# IAS_v006.net
KiCad netlist of a schematic drawn in EAGLE
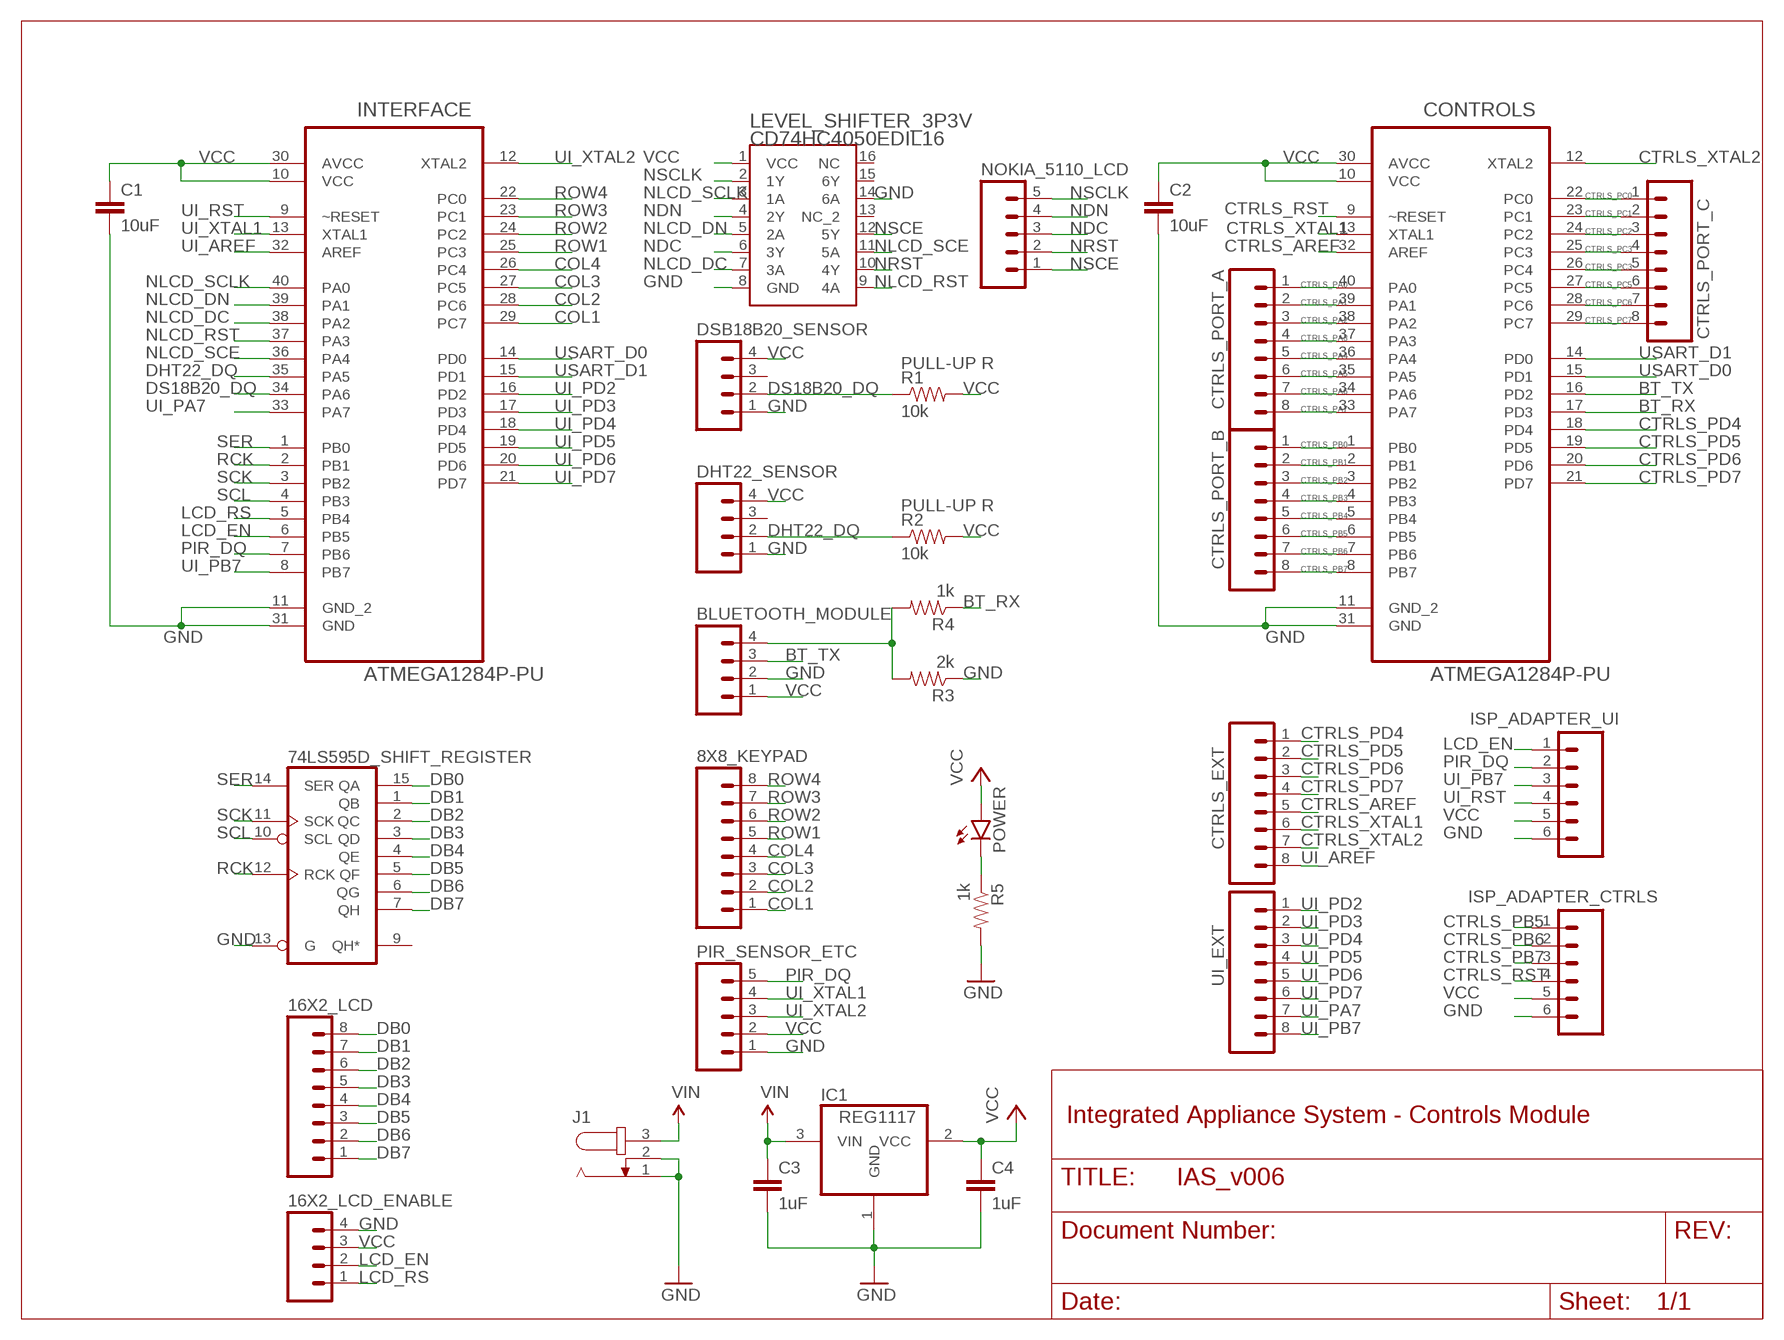
[diagram p0: schematic, sheet 1]

(export (version "E")
  (design (tool "Eeschema 10.0.6"))
  (components
    (comp (ref "8X8_KEYPAD")
      (value "M08")
      (footprint "eagle-import:1X08_ROUND")
      (libsource (lib "eagle-import") (part "M08"))
    )
    (comp (ref "16X2_LCD")
      (value "M08")
      (footprint "eagle-import:1X08_ROUND")
      (libsource (lib "eagle-import") (part "M08"))
    )
    (comp (ref "16X2_LCD_ENABLE")
      (value "M04NO_SILK_ALL_ROUND")
      (footprint "eagle-import:1X04_NO_SILK_ALL_ROUND")
      (libsource (lib "eagle-import") (part "M04NO_SILK_ALL_ROUND"))
    )
    (comp (ref "74LS595D_SHIFT_REGISTER")
      (value "74LS595N")
      (footprint "eagle-import:DIL16")
      (fields (field (name "MPN") "SN74LS595D"))
      (libsource (lib "eagle-import") (part "74595NLS"))
    )
    (comp (ref "BLUETOOTH_MODULE")
      (value "M04NO_SILK_ALL_ROUND")
      (footprint "eagle-import:1X04_NO_SILK_ALL_ROUND")
      (libsource (lib "eagle-import") (part "M04NO_SILK_ALL_ROUND"))
    )
    (comp (ref "C1")
      (value "10uF")
      (footprint "eagle-import:1206")
      (libsource (lib "eagle-import") (part "CAP1206"))
    )
    (comp (ref "C2")
      (value "10uF")
      (footprint "eagle-import:1206")
      (libsource (lib "eagle-import") (part "CAP1206"))
    )
    (comp (ref "C3")
      (value "1uF")
      (footprint "eagle-import:1206")
      (libsource (lib "eagle-import") (part "CAP1206"))
    )
    (comp (ref "C4")
      (value "1uF")
      (footprint "eagle-import:1206")
      (libsource (lib "eagle-import") (part "CAP1206"))
    )
    (comp (ref "CONTROLS")
      (value "ATMEGA1284P-PU")
      (footprint "eagle-import:DIP254P1524X483-40")
      (libsource (lib "eagle-import") (part "ATMEGA1284P-PU"))
    )
    (comp (ref "CTRLS_EXT")
      (value "M08")
      (footprint "eagle-import:1X08_ROUND")
      (libsource (lib "eagle-import") (part "M08"))
    )
    (comp (ref "CTRLS_PORT_A")
      (value "M08")
      (footprint "eagle-import:1X08_ROUND")
      (libsource (lib "eagle-import") (part "M08"))
    )
    (comp (ref "CTRLS_PORT_B")
      (value "M08")
      (footprint "eagle-import:1X08_ROUND")
      (libsource (lib "eagle-import") (part "M08"))
    )
    (comp (ref "CTRLS_PORT_C")
      (value "M08")
      (footprint "eagle-import:1X08_ROUND")
      (libsource (lib "eagle-import") (part "M08"))
    )
    (comp (ref "DHT22_SENSOR")
      (value "M04NO_SILK_ALL_ROUND")
      (footprint "eagle-import:1X04_NO_SILK_ALL_ROUND")
      (libsource (lib "eagle-import") (part "M04NO_SILK_ALL_ROUND"))
    )
    (comp (ref "DSB18B20_SENSOR")
      (value "M04NO_SILK_ALL_ROUND")
      (footprint "eagle-import:1X04_NO_SILK_ALL_ROUND")
      (libsource (lib "eagle-import") (part "M04NO_SILK_ALL_ROUND"))
    )
    (comp (ref "IC1")
      (value "REG1117")
      (footprint "eagle-import:SOT223")
      (libsource (lib "eagle-import") (part "REG1117"))
    )
    (comp (ref "INTERFACE")
      (value "ATMEGA1284P-PU")
      (footprint "eagle-import:DIP254P1524X483-40")
      (libsource (lib "eagle-import") (part "ATMEGA1284P-PU"))
    )
    (comp (ref "ISP_ADAPTER_CTRLS")
      (value "M06SILK_FEMALE_PTH")
      (footprint "eagle-import:1X06")
      (libsource (lib "eagle-import") (part "M06SILK_FEMALE_PTH"))
    )
    (comp (ref "ISP_ADAPTER_UI")
      (value "M06SILK_FEMALE_PTH")
      (footprint "eagle-import:1X06")
      (libsource (lib "eagle-import") (part "M06SILK_FEMALE_PTH"))
    )
    (comp (ref "J1")
      (value "JACK-PLUG0")
      (footprint "eagle-import:SPC4077")
      (libsource (lib "eagle-import") (part "JACK-PLUG0"))
    )
    (comp (ref "LEVEL_SHIFTER_3P3V")
      (value "CD74HC4050EDIL16")
      (footprint "eagle-import:DIL16")
      (fields
        (field (name "MANUFACTURER_PART_NUMBER") "CD74HC4050EE4")
        (field (name "RSPARTNUMBER") "7092573")
        (field (name "COPYRIGHT") "Copyright (C) 2015 Accelerated Designs. All rights reserved")
      )
      (libsource (lib "eagle-import") (part "CD74HC4050EDIL16"))
    )
    (comp (ref "NOKIA_5110_LCD")
      (value "M05PTH")
      (footprint "eagle-import:1X05")
      (libsource (lib "eagle-import") (part "M05PTH"))
    )
    (comp (ref "PIR_SENSOR_ETC")
      (value "M05PTH")
      (footprint "eagle-import:1X05")
      (libsource (lib "eagle-import") (part "M05PTH"))
    )
    (comp (ref "POWER")
      (value "LED3MM")
      (footprint "eagle-import:LED3MM")
      (libsource (lib "eagle-import") (part "LED3MM"))
    )
    (comp (ref "R1")
      (value "10k")
      (footprint "eagle-import:1206")
      (libsource (lib "eagle-import") (part "RESISTOR1206"))
    )
    (comp (ref "R2")
      (value "10k")
      (footprint "eagle-import:1206")
      (libsource (lib "eagle-import") (part "RESISTOR1206"))
    )
    (comp (ref "R3")
      (value "2k")
      (footprint "eagle-import:1206")
      (libsource (lib "eagle-import") (part "RESISTOR1206"))
    )
    (comp (ref "R4")
      (value "1k")
      (footprint "eagle-import:1206")
      (libsource (lib "eagle-import") (part "RESISTOR1206"))
    )
    (comp (ref "R5")
      (value "1k")
      (footprint "eagle-import:1206")
      (libsource (lib "eagle-import") (part "RESISTOR1206"))
    )
    (comp (ref "UI_EXT")
      (value "M08")
      (footprint "eagle-import:1X08_ROUND")
      (libsource (lib "eagle-import") (part "M08"))
    )
  )
  (nets
    (net (code "1") (name "/BT_RX") (class "Default")
      (node (ref "CONTROLS") (pin "17") (pinfunction "PD3_17") (pintype "bidirectional"))
      (node (ref "R4") (pin "1") (pinfunction "1_1") (pintype "passive"))
    )
    (net (code "2") (name "/BT_TX") (class "Default")
      (node (ref "BLUETOOTH_MODULE") (pin "3") (pinfunction "3_3") (pintype "passive"))
      (node (ref "CONTROLS") (pin "16") (pinfunction "PD2_16") (pintype "bidirectional"))
    )
    (net (code "3") (name "/COL1") (class "Default")
      (node (ref "8X8_KEYPAD") (pin "1") (pinfunction "1_1") (pintype "passive"))
      (node (ref "INTERFACE") (pin "29") (pinfunction "PC7_29") (pintype "bidirectional"))
    )
    (net (code "4") (name "/COL2") (class "Default")
      (node (ref "8X8_KEYPAD") (pin "2") (pinfunction "2_2") (pintype "passive"))
      (node (ref "INTERFACE") (pin "28") (pinfunction "PC6_28") (pintype "bidirectional"))
    )
    (net (code "5") (name "/COL3") (class "Default")
      (node (ref "8X8_KEYPAD") (pin "3") (pinfunction "3_3") (pintype "passive"))
      (node (ref "INTERFACE") (pin "27") (pinfunction "PC5_27") (pintype "bidirectional"))
    )
    (net (code "6") (name "/COL4") (class "Default")
      (node (ref "8X8_KEYPAD") (pin "4") (pinfunction "4_4") (pintype "passive"))
      (node (ref "INTERFACE") (pin "26") (pinfunction "PC4_26") (pintype "bidirectional"))
    )
    (net (code "7") (name "/CTRLS_AREF") (class "Default")
      (node (ref "CONTROLS") (pin "32") (pinfunction "AREF_32") (pintype "input"))
      (node (ref "CTRLS_EXT") (pin "5") (pinfunction "5_5") (pintype "passive"))
    )
    (net (code "8") (name "/CTRLS_PA0") (class "Default")
      (node (ref "CONTROLS") (pin "40") (pinfunction "PA0_40") (pintype "bidirectional"))
      (node (ref "CTRLS_PORT_A") (pin "1") (pinfunction "1_1") (pintype "passive"))
    )
    (net (code "9") (name "/CTRLS_PA1") (class "Default")
      (node (ref "CONTROLS") (pin "39") (pinfunction "PA1_39") (pintype "bidirectional"))
      (node (ref "CTRLS_PORT_A") (pin "2") (pinfunction "2_2") (pintype "passive"))
    )
    (net (code "10") (name "/CTRLS_PA2") (class "Default")
      (node (ref "CONTROLS") (pin "38") (pinfunction "PA2_38") (pintype "bidirectional"))
      (node (ref "CTRLS_PORT_A") (pin "3") (pinfunction "3_3") (pintype "passive"))
    )
    (net (code "11") (name "/CTRLS_PA3") (class "Default")
      (node (ref "CONTROLS") (pin "37") (pinfunction "PA3_37") (pintype "bidirectional"))
      (node (ref "CTRLS_PORT_A") (pin "4") (pinfunction "4_4") (pintype "passive"))
    )
    (net (code "12") (name "/CTRLS_PA4") (class "Default")
      (node (ref "CONTROLS") (pin "36") (pinfunction "PA4_36") (pintype "bidirectional"))
      (node (ref "CTRLS_PORT_A") (pin "5") (pinfunction "5_5") (pintype "passive"))
    )
    (net (code "13") (name "/CTRLS_PA5") (class "Default")
      (node (ref "CONTROLS") (pin "35") (pinfunction "PA5_35") (pintype "bidirectional"))
      (node (ref "CTRLS_PORT_A") (pin "6") (pinfunction "6_6") (pintype "passive"))
    )
    (net (code "14") (name "/CTRLS_PA6") (class "Default")
      (node (ref "CONTROLS") (pin "34") (pinfunction "PA6_34") (pintype "bidirectional"))
      (node (ref "CTRLS_PORT_A") (pin "7") (pinfunction "7_7") (pintype "passive"))
    )
    (net (code "15") (name "/CTRLS_PA7") (class "Default")
      (node (ref "CONTROLS") (pin "33") (pinfunction "PA7_33") (pintype "bidirectional"))
      (node (ref "CTRLS_PORT_A") (pin "8") (pinfunction "8_8") (pintype "passive"))
    )
    (net (code "16") (name "/CTRLS_PB0") (class "Default")
      (node (ref "CONTROLS") (pin "1") (pinfunction "PB0_1") (pintype "bidirectional"))
      (node (ref "CTRLS_PORT_B") (pin "1") (pinfunction "1_1") (pintype "passive"))
    )
    (net (code "17") (name "/CTRLS_PB1") (class "Default")
      (node (ref "CONTROLS") (pin "2") (pinfunction "PB1_2") (pintype "bidirectional"))
      (node (ref "CTRLS_PORT_B") (pin "2") (pinfunction "2_2") (pintype "passive"))
    )
    (net (code "18") (name "/CTRLS_PB2") (class "Default")
      (node (ref "CONTROLS") (pin "3") (pinfunction "PB2_3") (pintype "bidirectional"))
      (node (ref "CTRLS_PORT_B") (pin "3") (pinfunction "3_3") (pintype "passive"))
    )
    (net (code "19") (name "/CTRLS_PB3") (class "Default")
      (node (ref "CONTROLS") (pin "4") (pinfunction "PB3_4") (pintype "bidirectional"))
      (node (ref "CTRLS_PORT_B") (pin "4") (pinfunction "4_4") (pintype "passive"))
    )
    (net (code "20") (name "/CTRLS_PB4") (class "Default")
      (node (ref "CONTROLS") (pin "5") (pinfunction "PB4_5") (pintype "bidirectional"))
      (node (ref "CTRLS_PORT_B") (pin "5") (pinfunction "5_5") (pintype "passive"))
    )
    (net (code "21") (name "/CTRLS_PB5") (class "Default")
      (node (ref "CONTROLS") (pin "6") (pinfunction "PB5_6") (pintype "bidirectional"))
      (node (ref "CTRLS_PORT_B") (pin "6") (pinfunction "6_6") (pintype "passive"))
      (node (ref "ISP_ADAPTER_CTRLS") (pin "1") (pinfunction "1_1") (pintype "passive"))
    )
    (net (code "22") (name "/CTRLS_PB6") (class "Default")
      (node (ref "CONTROLS") (pin "7") (pinfunction "PB6_7") (pintype "bidirectional"))
      (node (ref "CTRLS_PORT_B") (pin "7") (pinfunction "7_7") (pintype "passive"))
      (node (ref "ISP_ADAPTER_CTRLS") (pin "2") (pinfunction "2_2") (pintype "passive"))
    )
    (net (code "23") (name "/CTRLS_PB7") (class "Default")
      (node (ref "CONTROLS") (pin "8") (pinfunction "PB7_8") (pintype "bidirectional"))
      (node (ref "CTRLS_PORT_B") (pin "8") (pinfunction "8_8") (pintype "passive"))
      (node (ref "ISP_ADAPTER_CTRLS") (pin "3") (pinfunction "3_3") (pintype "passive"))
    )
    (net (code "24") (name "/CTRLS_PC0") (class "Default")
      (node (ref "CONTROLS") (pin "22") (pinfunction "PC0_22") (pintype "bidirectional"))
      (node (ref "CTRLS_PORT_C") (pin "1") (pinfunction "1_1") (pintype "passive"))
    )
    (net (code "25") (name "/CTRLS_PC1") (class "Default")
      (node (ref "CONTROLS") (pin "23") (pinfunction "PC1_23") (pintype "bidirectional"))
      (node (ref "CTRLS_PORT_C") (pin "2") (pinfunction "2_2") (pintype "passive"))
    )
    (net (code "26") (name "/CTRLS_PC2") (class "Default")
      (node (ref "CONTROLS") (pin "24") (pinfunction "PC2_24") (pintype "bidirectional"))
      (node (ref "CTRLS_PORT_C") (pin "3") (pinfunction "3_3") (pintype "passive"))
    )
    (net (code "27") (name "/CTRLS_PC3") (class "Default")
      (node (ref "CONTROLS") (pin "25") (pinfunction "PC3_25") (pintype "bidirectional"))
      (node (ref "CTRLS_PORT_C") (pin "4") (pinfunction "4_4") (pintype "passive"))
    )
    (net (code "28") (name "/CTRLS_PC5") (class "Default")
      (node (ref "CONTROLS") (pin "27") (pinfunction "PC5_27") (pintype "bidirectional"))
      (node (ref "CTRLS_PORT_C") (pin "6") (pinfunction "6_6") (pintype "passive"))
    )
    (net (code "29") (name "/CTRLS_PC6") (class "Default")
      (node (ref "CONTROLS") (pin "28") (pinfunction "PC6_28") (pintype "bidirectional"))
      (node (ref "CTRLS_PORT_C") (pin "7") (pinfunction "7_7") (pintype "passive"))
    )
    (net (code "30") (name "/CTRLS_PC7") (class "Default")
      (node (ref "CONTROLS") (pin "29") (pinfunction "PC7_29") (pintype "bidirectional"))
      (node (ref "CTRLS_PORT_C") (pin "8") (pinfunction "8_8") (pintype "passive"))
    )
    (net (code "31") (name "/CTRLS_PD4") (class "Default")
      (node (ref "CONTROLS") (pin "18") (pinfunction "PD4_18") (pintype "bidirectional"))
      (node (ref "CTRLS_EXT") (pin "1") (pinfunction "1_1") (pintype "passive"))
    )
    (net (code "32") (name "/CTRLS_PD5") (class "Default")
      (node (ref "CONTROLS") (pin "19") (pinfunction "PD5_19") (pintype "bidirectional"))
      (node (ref "CTRLS_EXT") (pin "2") (pinfunction "2_2") (pintype "passive"))
    )
    (net (code "33") (name "/CTRLS_PD6") (class "Default")
      (node (ref "CONTROLS") (pin "20") (pinfunction "PD6_20") (pintype "bidirectional"))
      (node (ref "CTRLS_EXT") (pin "3") (pinfunction "3_3") (pintype "passive"))
    )
    (net (code "34") (name "/CTRLS_PD7") (class "Default")
      (node (ref "CONTROLS") (pin "21") (pinfunction "PD7_21") (pintype "bidirectional"))
      (node (ref "CTRLS_EXT") (pin "4") (pinfunction "4_4") (pintype "passive"))
    )
    (net (code "35") (name "/CTRLS_RST") (class "Default")
      (node (ref "CONTROLS") (pin "9") (pinfunction "~{RESET}_9") (pintype "input"))
      (node (ref "ISP_ADAPTER_CTRLS") (pin "4") (pinfunction "4_4") (pintype "passive"))
    )
    (net (code "36") (name "/CTRLS_XTAL1") (class "Default")
      (node (ref "CONTROLS") (pin "13") (pinfunction "XTAL1_13") (pintype "input"))
      (node (ref "CTRLS_EXT") (pin "6") (pinfunction "6_6") (pintype "passive"))
    )
    (net (code "37") (name "/CTRLS_XTAL2") (class "Default")
      (node (ref "CONTROLS") (pin "12") (pinfunction "XTAL2_12") (pintype "output"))
      (node (ref "CTRLS_EXT") (pin "7") (pinfunction "7_7") (pintype "passive"))
    )
    (net (code "38") (name "/DB0") (class "Default")
      (node (ref "16X2_LCD") (pin "8") (pinfunction "8_8") (pintype "passive"))
      (node (ref "74LS595D_SHIFT_REGISTER") (pin "15") (pinfunction "QA_15") (pintype "tri_state"))
    )
    (net (code "39") (name "/DB1") (class "Default")
      (node (ref "16X2_LCD") (pin "7") (pinfunction "7_7") (pintype "passive"))
      (node (ref "74LS595D_SHIFT_REGISTER") (pin "1") (pinfunction "QB_1") (pintype "tri_state"))
    )
    (net (code "40") (name "/DB2") (class "Default")
      (node (ref "16X2_LCD") (pin "6") (pinfunction "6_6") (pintype "passive"))
      (node (ref "74LS595D_SHIFT_REGISTER") (pin "2") (pinfunction "QC_2") (pintype "tri_state"))
    )
    (net (code "41") (name "/DB3") (class "Default")
      (node (ref "16X2_LCD") (pin "5") (pinfunction "5_5") (pintype "passive"))
      (node (ref "74LS595D_SHIFT_REGISTER") (pin "3") (pinfunction "QD_3") (pintype "tri_state"))
    )
    (net (code "42") (name "/DB4") (class "Default")
      (node (ref "16X2_LCD") (pin "4") (pinfunction "4_4") (pintype "passive"))
      (node (ref "74LS595D_SHIFT_REGISTER") (pin "4") (pinfunction "QE_4") (pintype "tri_state"))
    )
    (net (code "43") (name "/DB5") (class "Default")
      (node (ref "16X2_LCD") (pin "3") (pinfunction "3_3") (pintype "passive"))
      (node (ref "74LS595D_SHIFT_REGISTER") (pin "5") (pinfunction "QF_5") (pintype "tri_state"))
    )
    (net (code "44") (name "/DB6") (class "Default")
      (node (ref "16X2_LCD") (pin "2") (pinfunction "2_2") (pintype "passive"))
      (node (ref "74LS595D_SHIFT_REGISTER") (pin "6") (pinfunction "QG_6") (pintype "tri_state"))
    )
    (net (code "45") (name "/DB7") (class "Default")
      (node (ref "16X2_LCD") (pin "1") (pinfunction "1_1") (pintype "passive"))
      (node (ref "74LS595D_SHIFT_REGISTER") (pin "7") (pinfunction "QH_7") (pintype "tri_state"))
    )
    (net (code "46") (name "/DHT22_DQ") (class "Default")
      (node (ref "DHT22_SENSOR") (pin "2") (pinfunction "2_2") (pintype "passive"))
      (node (ref "INTERFACE") (pin "35") (pinfunction "PA5_35") (pintype "bidirectional"))
      (node (ref "R2") (pin "1") (pinfunction "1_1") (pintype "passive"))
    )
    (net (code "47") (name "/DS18B20_DQ") (class "Default")
      (node (ref "DSB18B20_SENSOR") (pin "2") (pinfunction "2_2") (pintype "passive"))
      (node (ref "INTERFACE") (pin "34") (pinfunction "PA6_34") (pintype "bidirectional"))
      (node (ref "R1") (pin "1") (pinfunction "1_1") (pintype "passive"))
    )
    (net (code "48") (name "/LCD_EN") (class "Default")
      (node (ref "16X2_LCD_ENABLE") (pin "2") (pinfunction "2_2") (pintype "passive"))
      (node (ref "INTERFACE") (pin "6") (pinfunction "PB5_6") (pintype "bidirectional"))
      (node (ref "ISP_ADAPTER_UI") (pin "1") (pinfunction "1_1") (pintype "passive"))
    )
    (net (code "49") (name "/LCD_RS") (class "Default")
      (node (ref "16X2_LCD_ENABLE") (pin "1") (pinfunction "1_1") (pintype "passive"))
      (node (ref "INTERFACE") (pin "5") (pinfunction "PB4_5") (pintype "bidirectional"))
    )
    (net (code "50") (name "/NDC") (class "Default")
      (node (ref "LEVEL_SHIFTER_3P3V") (pin "6") (pinfunction "3Y_6") (pintype "output"))
      (node (ref "NOKIA_5110_LCD") (pin "3") (pinfunction "3_3") (pintype "passive"))
    )
    (net (code "51") (name "/NDN") (class "Default")
      (node (ref "LEVEL_SHIFTER_3P3V") (pin "4") (pinfunction "2Y_4") (pintype "output"))
      (node (ref "NOKIA_5110_LCD") (pin "4") (pinfunction "4_4") (pintype "passive"))
    )
    (net (code "52") (name "/NLCD_DC") (class "Default")
      (node (ref "INTERFACE") (pin "38") (pinfunction "PA2_38") (pintype "bidirectional"))
      (node (ref "LEVEL_SHIFTER_3P3V") (pin "7") (pinfunction "3A_7") (pintype "input"))
    )
    (net (code "53") (name "/NLCD_DN") (class "Default")
      (node (ref "INTERFACE") (pin "39") (pinfunction "PA1_39") (pintype "bidirectional"))
      (node (ref "LEVEL_SHIFTER_3P3V") (pin "5") (pinfunction "2A_5") (pintype "input"))
    )
    (net (code "54") (name "/NLCD_RST") (class "Default")
      (node (ref "INTERFACE") (pin "37") (pinfunction "PA3_37") (pintype "bidirectional"))
      (node (ref "LEVEL_SHIFTER_3P3V") (pin "9") (pinfunction "4A_9") (pintype "input"))
    )
    (net (code "55") (name "/NLCD_SCE") (class "Default")
      (node (ref "INTERFACE") (pin "36") (pinfunction "PA4_36") (pintype "bidirectional"))
      (node (ref "LEVEL_SHIFTER_3P3V") (pin "11") (pinfunction "5A_11") (pintype "input"))
    )
    (net (code "56") (name "/NLCD_SCLK") (class "Default")
      (node (ref "INTERFACE") (pin "40") (pinfunction "PA0_40") (pintype "bidirectional"))
      (node (ref "LEVEL_SHIFTER_3P3V") (pin "3") (pinfunction "1A_3") (pintype "input"))
    )
    (net (code "57") (name "/NRST") (class "Default")
      (node (ref "LEVEL_SHIFTER_3P3V") (pin "10") (pinfunction "4Y_10") (pintype "output"))
      (node (ref "NOKIA_5110_LCD") (pin "2") (pinfunction "2_2") (pintype "passive"))
    )
    (net (code "58") (name "/NSCE") (class "Default")
      (node (ref "LEVEL_SHIFTER_3P3V") (pin "12") (pinfunction "5Y_12") (pintype "output"))
      (node (ref "NOKIA_5110_LCD") (pin "1") (pinfunction "1_1") (pintype "passive"))
    )
    (net (code "59") (name "/NSCLK") (class "Default")
      (node (ref "LEVEL_SHIFTER_3P3V") (pin "2") (pinfunction "1Y_2") (pintype "output"))
      (node (ref "NOKIA_5110_LCD") (pin "5") (pinfunction "5_5") (pintype "passive"))
    )
    (net (code "60") (name "/PIR_DQ") (class "Default")
      (node (ref "INTERFACE") (pin "7") (pinfunction "PB6_7") (pintype "bidirectional"))
      (node (ref "ISP_ADAPTER_UI") (pin "2") (pinfunction "2_2") (pintype "passive"))
      (node (ref "PIR_SENSOR_ETC") (pin "5") (pinfunction "5_5") (pintype "passive"))
    )
    (net (code "61") (name "/RCK") (class "Default")
      (node (ref "74LS595D_SHIFT_REGISTER") (pin "12") (pinfunction "RCK_12") (pintype "input"))
      (node (ref "INTERFACE") (pin "2") (pinfunction "PB1_2") (pintype "bidirectional"))
    )
    (net (code "62") (name "/ROW1") (class "Default")
      (node (ref "8X8_KEYPAD") (pin "5") (pinfunction "5_5") (pintype "passive"))
      (node (ref "INTERFACE") (pin "25") (pinfunction "PC3_25") (pintype "bidirectional"))
    )
    (net (code "63") (name "/ROW2") (class "Default")
      (node (ref "8X8_KEYPAD") (pin "6") (pinfunction "6_6") (pintype "passive"))
      (node (ref "INTERFACE") (pin "24") (pinfunction "PC2_24") (pintype "bidirectional"))
    )
    (net (code "64") (name "/ROW3") (class "Default")
      (node (ref "8X8_KEYPAD") (pin "7") (pinfunction "7_7") (pintype "passive"))
      (node (ref "INTERFACE") (pin "23") (pinfunction "PC1_23") (pintype "bidirectional"))
    )
    (net (code "65") (name "/ROW4") (class "Default")
      (node (ref "8X8_KEYPAD") (pin "8") (pinfunction "8_8") (pintype "passive"))
      (node (ref "INTERFACE") (pin "22") (pinfunction "PC0_22") (pintype "bidirectional"))
    )
    (net (code "66") (name "/SCK") (class "Default")
      (node (ref "74LS595D_SHIFT_REGISTER") (pin "11") (pinfunction "SCK_11") (pintype "input"))
      (node (ref "INTERFACE") (pin "3") (pinfunction "PB2_3") (pintype "bidirectional"))
    )
    (net (code "67") (name "/SCL") (class "Default")
      (node (ref "74LS595D_SHIFT_REGISTER") (pin "10") (pinfunction "SCL_10") (pintype "input"))
      (node (ref "INTERFACE") (pin "4") (pinfunction "PB3_4") (pintype "bidirectional"))
    )
    (net (code "68") (name "/SER") (class "Default")
      (node (ref "74LS595D_SHIFT_REGISTER") (pin "14") (pinfunction "SER_14") (pintype "input"))
      (node (ref "INTERFACE") (pin "1") (pinfunction "PB0_1") (pintype "bidirectional"))
    )
    (net (code "69") (name "/UI_AREF") (class "Default")
      (node (ref "CTRLS_EXT") (pin "8") (pinfunction "8_8") (pintype "passive"))
      (node (ref "INTERFACE") (pin "32") (pinfunction "AREF_32") (pintype "input"))
    )
    (net (code "70") (name "/UI_PA7") (class "Default")
      (node (ref "INTERFACE") (pin "33") (pinfunction "PA7_33") (pintype "bidirectional"))
      (node (ref "UI_EXT") (pin "7") (pinfunction "7_7") (pintype "passive"))
    )
    (net (code "71") (name "/UI_PB7") (class "Default")
      (node (ref "INTERFACE") (pin "8") (pinfunction "PB7_8") (pintype "bidirectional"))
      (node (ref "ISP_ADAPTER_UI") (pin "3") (pinfunction "3_3") (pintype "passive"))
      (node (ref "UI_EXT") (pin "8") (pinfunction "8_8") (pintype "passive"))
    )
    (net (code "72") (name "/UI_PD2") (class "Default")
      (node (ref "INTERFACE") (pin "16") (pinfunction "PD2_16") (pintype "bidirectional"))
      (node (ref "UI_EXT") (pin "1") (pinfunction "1_1") (pintype "passive"))
    )
    (net (code "73") (name "/UI_PD3") (class "Default")
      (node (ref "INTERFACE") (pin "17") (pinfunction "PD3_17") (pintype "bidirectional"))
      (node (ref "UI_EXT") (pin "2") (pinfunction "2_2") (pintype "passive"))
    )
    (net (code "74") (name "/UI_PD4") (class "Default")
      (node (ref "INTERFACE") (pin "18") (pinfunction "PD4_18") (pintype "bidirectional"))
      (node (ref "UI_EXT") (pin "3") (pinfunction "3_3") (pintype "passive"))
    )
    (net (code "75") (name "/UI_PD5") (class "Default")
      (node (ref "INTERFACE") (pin "19") (pinfunction "PD5_19") (pintype "bidirectional"))
      (node (ref "UI_EXT") (pin "4") (pinfunction "4_4") (pintype "passive"))
    )
    (net (code "76") (name "/UI_PD6") (class "Default")
      (node (ref "INTERFACE") (pin "20") (pinfunction "PD6_20") (pintype "bidirectional"))
      (node (ref "UI_EXT") (pin "5") (pinfunction "5_5") (pintype "passive"))
    )
    (net (code "77") (name "/UI_PD7") (class "Default")
      (node (ref "INTERFACE") (pin "21") (pinfunction "PD7_21") (pintype "bidirectional"))
      (node (ref "UI_EXT") (pin "6") (pinfunction "6_6") (pintype "passive"))
    )
    (net (code "78") (name "/UI_RST") (class "Default")
      (node (ref "INTERFACE") (pin "9") (pinfunction "~{RESET}_9") (pintype "input"))
      (node (ref "ISP_ADAPTER_UI") (pin "4") (pinfunction "4_4") (pintype "passive"))
    )
    (net (code "79") (name "/UI_XTAL1") (class "Default")
      (node (ref "INTERFACE") (pin "13") (pinfunction "XTAL1_13") (pintype "input"))
      (node (ref "PIR_SENSOR_ETC") (pin "4") (pinfunction "4_4") (pintype "passive"))
    )
    (net (code "80") (name "/UI_XTAL2") (class "Default")
      (node (ref "INTERFACE") (pin "12") (pinfunction "XTAL2_12") (pintype "output"))
      (node (ref "PIR_SENSOR_ETC") (pin "3") (pinfunction "3_3") (pintype "passive"))
    )
    (net (code "81") (name "/USART_D0") (class "Default")
      (node (ref "CONTROLS") (pin "15") (pinfunction "PD1_15") (pintype "bidirectional"))
      (node (ref "INTERFACE") (pin "14") (pinfunction "PD0_14") (pintype "bidirectional"))
    )
    (net (code "82") (name "/USART_D1") (class "Default")
      (node (ref "CONTROLS") (pin "14") (pinfunction "PD0_14") (pintype "bidirectional"))
      (node (ref "INTERFACE") (pin "15") (pinfunction "PD1_15") (pintype "bidirectional"))
    )
    (net (code "83") (name "GND") (class "Default")
      (node (ref "16X2_LCD_ENABLE") (pin "4") (pinfunction "4_4") (pintype "passive"))
      (node (ref "74LS595D_SHIFT_REGISTER") (pin "13") (pinfunction "G_13") (pintype "input"))
      (node (ref "BLUETOOTH_MODULE") (pin "2") (pinfunction "2_2") (pintype "passive"))
      (node (ref "C1") (pin "2") (pinfunction "2_2") (pintype "passive"))
      (node (ref "C2") (pin "2") (pinfunction "2_2") (pintype "passive"))
      (node (ref "C3") (pin "2") (pinfunction "2_2") (pintype "passive"))
      (node (ref "C4") (pin "2") (pinfunction "2_2") (pintype "passive"))
      (node (ref "CONTROLS") (pin "11") (pinfunction "GND_2_11") (pintype "passive"))
      (node (ref "CONTROLS") (pin "31") (pinfunction "GND_31") (pintype "passive"))
      (node (ref "DHT22_SENSOR") (pin "1") (pinfunction "1_1") (pintype "passive"))
      (node (ref "DSB18B20_SENSOR") (pin "1") (pinfunction "1_1") (pintype "passive"))
      (node (ref "IC1") (pin "1") (pinfunction "GND_1") (pintype "power_in"))
      (node (ref "INTERFACE") (pin "11") (pinfunction "GND_2_11") (pintype "passive"))
      (node (ref "INTERFACE") (pin "31") (pinfunction "GND_31") (pintype "passive"))
      (node (ref "ISP_ADAPTER_CTRLS") (pin "6") (pinfunction "6_6") (pintype "passive"))
      (node (ref "ISP_ADAPTER_UI") (pin "6") (pinfunction "6_6") (pintype "passive"))
      (node (ref "J1") (pin "1") (pinfunction "1_1") (pintype "passive"))
      (node (ref "J1") (pin "2") (pinfunction "2_2") (pintype "passive"))
      (node (ref "LEVEL_SHIFTER_3P3V") (pin "14") (pinfunction "6A_14") (pintype "input"))
      (node (ref "LEVEL_SHIFTER_3P3V") (pin "8") (pinfunction "GND_8") (pintype "passive"))
      (node (ref "PIR_SENSOR_ETC") (pin "1") (pinfunction "1_1") (pintype "passive"))
      (node (ref "R3") (pin "1") (pinfunction "1_1") (pintype "passive"))
      (node (ref "R5") (pin "2") (pinfunction "2_2") (pintype "passive"))
    )
    (net (code "84") (name "Net-(BLUETOOTH_MODULE-Pad4)") (class "Default")
      (node (ref "BLUETOOTH_MODULE") (pin "4") (pinfunction "4_4") (pintype "passive"))
      (node (ref "R3") (pin "2") (pinfunction "2_2") (pintype "passive"))
      (node (ref "R4") (pin "2") (pinfunction "2_2") (pintype "passive"))
    )
    (net (code "85") (name "Net-(CONTROLS-PC4)") (class "Default")
      (node (ref "CONTROLS") (pin "26") (pinfunction "PC4_26") (pintype "bidirectional"))
      (node (ref "CTRLS_PORT_C") (pin "5") (pinfunction "5_5") (pintype "passive"))
    )
    (net (code "86") (name "Net-(POWER-C)") (class "Default")
      (node (ref "POWER") (pin "K") (pinfunction "C_K") (pintype "passive"))
      (node (ref "R5") (pin "1") (pinfunction "1_1") (pintype "passive"))
    )
    (net (code "87") (name "VCC") (class "Default")
      (node (ref "16X2_LCD_ENABLE") (pin "3") (pinfunction "3_3") (pintype "passive"))
      (node (ref "BLUETOOTH_MODULE") (pin "1") (pinfunction "1_1") (pintype "passive"))
      (node (ref "C1") (pin "1") (pinfunction "1_1") (pintype "passive"))
      (node (ref "C2") (pin "1") (pinfunction "1_1") (pintype "passive"))
      (node (ref "C4") (pin "1") (pinfunction "1_1") (pintype "passive"))
      (node (ref "CONTROLS") (pin "10") (pinfunction "VCC_10") (pintype "power_in"))
      (node (ref "CONTROLS") (pin "30") (pinfunction "AVCC_30") (pintype "power_in"))
      (node (ref "DHT22_SENSOR") (pin "4") (pinfunction "4_4") (pintype "passive"))
      (node (ref "DSB18B20_SENSOR") (pin "4") (pinfunction "4_4") (pintype "passive"))
      (node (ref "IC1") (pin "2") (pinfunction "VCC_2") (pintype "power_in"))
      (node (ref "INTERFACE") (pin "10") (pinfunction "VCC_10") (pintype "power_in"))
      (node (ref "INTERFACE") (pin "30") (pinfunction "AVCC_30") (pintype "power_in"))
      (node (ref "ISP_ADAPTER_CTRLS") (pin "5") (pinfunction "5_5") (pintype "passive"))
      (node (ref "ISP_ADAPTER_UI") (pin "5") (pinfunction "5_5") (pintype "passive"))
      (node (ref "LEVEL_SHIFTER_3P3V") (pin "1") (pinfunction "VCC_1") (pintype "passive"))
      (node (ref "PIR_SENSOR_ETC") (pin "2") (pinfunction "2_2") (pintype "passive"))
      (node (ref "POWER") (pin "A") (pinfunction "A_A") (pintype "passive"))
      (node (ref "R1") (pin "2") (pinfunction "2_2") (pintype "passive"))
      (node (ref "R2") (pin "2") (pinfunction "2_2") (pintype "passive"))
    )
    (net (code "88") (name "VIN") (class "Default")
      (node (ref "C3") (pin "1") (pinfunction "1_1") (pintype "passive"))
      (node (ref "IC1") (pin "3") (pinfunction "VIN_3") (pintype "input"))
      (node (ref "J1") (pin "3") (pinfunction "3_3") (pintype "passive"))
    )
    (net (code "89") (name "unconnected-(74LS595D_SHIFT_REGISTERA-QH*-Pad9)") (class "Default")
      (node (ref "74LS595D_SHIFT_REGISTER") (pin "9") (pinfunction "QH*_9") (pintype "tri_state"))
    )
    (net (code "90") (name "unconnected-(DHT22_SENSOR-Pad3)") (class "Default")
      (node (ref "DHT22_SENSOR") (pin "3") (pinfunction "3_3") (pintype "passive"))
    )
    (net (code "91") (name "unconnected-(DSB18B20_SENSOR-Pad3)") (class "Default")
      (node (ref "DSB18B20_SENSOR") (pin "3") (pinfunction "3_3") (pintype "passive"))
    )
    (net (code "92") (name "unconnected-(LEVEL_SHIFTER_3P3V-6Y-Pad15)") (class "Default")
      (node (ref "LEVEL_SHIFTER_3P3V") (pin "15") (pinfunction "6Y_15") (pintype "output"))
    )
    (net (code "93") (name "unconnected-(LEVEL_SHIFTER_3P3V-NC-Pad16)") (class "Default")
      (node (ref "LEVEL_SHIFTER_3P3V") (pin "16") (pinfunction "NC_16") (pintype "no_connect"))
    )
    (net (code "94") (name "unconnected-(LEVEL_SHIFTER_3P3V-NC_2-Pad13)") (class "Default")
      (node (ref "LEVEL_SHIFTER_3P3V") (pin "13") (pinfunction "NC_2_13") (pintype "no_connect"))
    )
  )
)
